# Gyro.net
KiCad netlist of a schematic drawn in Altium Designer
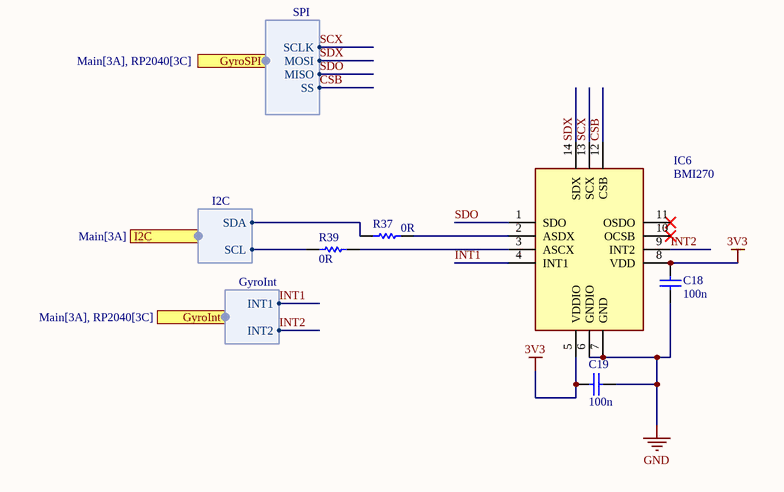
[diagram p0: Gyro.SchDoc]

(export (version "E")
  (design (tool "Eeschema 10.0.6"))
  (components
    (comp (ref "C18")
      (value "100n")
      (footprint "CAPC0603(1608)55_N")
      (description "Keramikvielschichtkondensator, SMD, Baureihe MC, ± 20%")
      (fields (field (name "MANUFACTURER") "Multicomp"))
      (libsource (lib "Standardbauteile") (part "Cap 100n"))
    )
    (comp (ref "C19")
      (value "100n")
      (footprint "CAPC0603(1608)55_N")
      (description "Keramikvielschichtkondensator, SMD, Baureihe MC, ± 20%")
      (fields (field (name "MANUFACTURER") "Multicomp"))
      (libsource (lib "Standardbauteile") (part "Cap 100n"))
    )
    (comp (ref "IC6")
      (value "BMI270")
      (footprint "QFN50P300X250X87-14N")
      (description "Integrated Circuit")
      (fields (field (name "MOUSER PART NUMBER") "262-BMI270"))
      (libsource (lib "Custom Components") (part "BMI270"))
    )
    (comp (ref "R37")
      (value "0R")
      (footprint "RESC1005X40X25NL05T10")
      (fields (field (name "MANUFACTURER") "Yageo / Phycomp") (field (name "PART NUMBER") "RC0402JR-070RL"))
      (libsource (lib "Altium Content Vault") (part "RES"))
    )
    (comp (ref "R39")
      (value "0R")
      (footprint "RESC1005X40X25NL05T10")
      (fields (field (name "MANUFACTURER") "Yageo / Phycomp") (field (name "PART NUMBER") "RC0402JR-070RL"))
      (libsource (lib "Altium Content Vault") (part "RES"))
    )
  )
  (nets
    (net (code "4") (name "/CSB") (class "Default")
      (node (ref "IC6") (pin "12") (pinfunction "CSB_12") (pintype "passive"))
    )
    (net (code "5") (name "/INT1") (class "Default")
      (node (ref "IC6") (pin "4") (pinfunction "INT1_4") (pintype "passive"))
    )
    (net (code "6") (name "/INT2") (class "Default")
      (node (ref "IC6") (pin "9") (pinfunction "INT2_9") (pintype "passive"))
    )
    (net (code "7") (name "/SCL") (class "Default")
      (node (ref "R39") (pin "1") (pinfunction "1_1") (pintype "passive"))
    )
    (net (code "8") (name "/SCX") (class "Default")
      (node (ref "IC6") (pin "13") (pinfunction "SCX_13") (pintype "passive"))
    )
    (net (code "9") (name "/SDA") (class "Default")
      (node (ref "R37") (pin "1") (pinfunction "1_1") (pintype "passive"))
    )
    (net (code "10") (name "/SDO") (class "Default")
      (node (ref "IC6") (pin "1") (pinfunction "SDO_1") (pintype "passive"))
    )
    (net (code "11") (name "/SDX") (class "Default")
      (node (ref "IC6") (pin "14") (pinfunction "SDX_14") (pintype "passive"))
    )
    (net (code "15") (name "3V3") (class "Default")
      (node (ref "C18") (pin "2") (pinfunction "2_2") (pintype "passive"))
      (node (ref "C19") (pin "2") (pinfunction "2_2") (pintype "passive"))
      (node (ref "IC6") (pin "5") (pinfunction "VDDIO_5") (pintype "passive"))
      (node (ref "IC6") (pin "8") (pinfunction "VDD_8") (pintype "passive"))
    )
    (net (code "16") (name "GND") (class "Default")
      (node (ref "C18") (pin "1") (pinfunction "1_1") (pintype "passive"))
      (node (ref "C19") (pin "1") (pinfunction "1_1") (pintype "passive"))
      (node (ref "IC6") (pin "6") (pinfunction "GNDIO_6") (pintype "passive"))
      (node (ref "IC6") (pin "7") (pinfunction "GND_7") (pintype "passive"))
    )
    (net (code "17") (name "Net-(IC6-ASCX)") (class "Default")
      (node (ref "IC6") (pin "3") (pinfunction "ASCX_3") (pintype "passive"))
      (node (ref "R39") (pin "2") (pinfunction "2_2") (pintype "passive"))
    )
    (net (code "18") (name "Net-(IC6-ASDX)") (class "Default")
      (node (ref "IC6") (pin "2") (pinfunction "ASDX_2") (pintype "passive"))
      (node (ref "R37") (pin "2") (pinfunction "2_2") (pintype "passive"))
    )
    (net (code "19") (name "unconnected-(IC6-OCSB-Pad10)") (class "Default")
      (node (ref "IC6") (pin "10") (pinfunction "OCSB_10") (pintype "passive+no_connect"))
    )
    (net (code "20") (name "unconnected-(IC6-OSDO-Pad11)") (class "Default")
      (node (ref "IC6") (pin "11") (pinfunction "OSDO_11") (pintype "passive+no_connect"))
    )
  )
)
